# Saules_kolektoriaus_valdiklis_v1_22.net
KiCad netlist of a schematic drawn in EAGLE
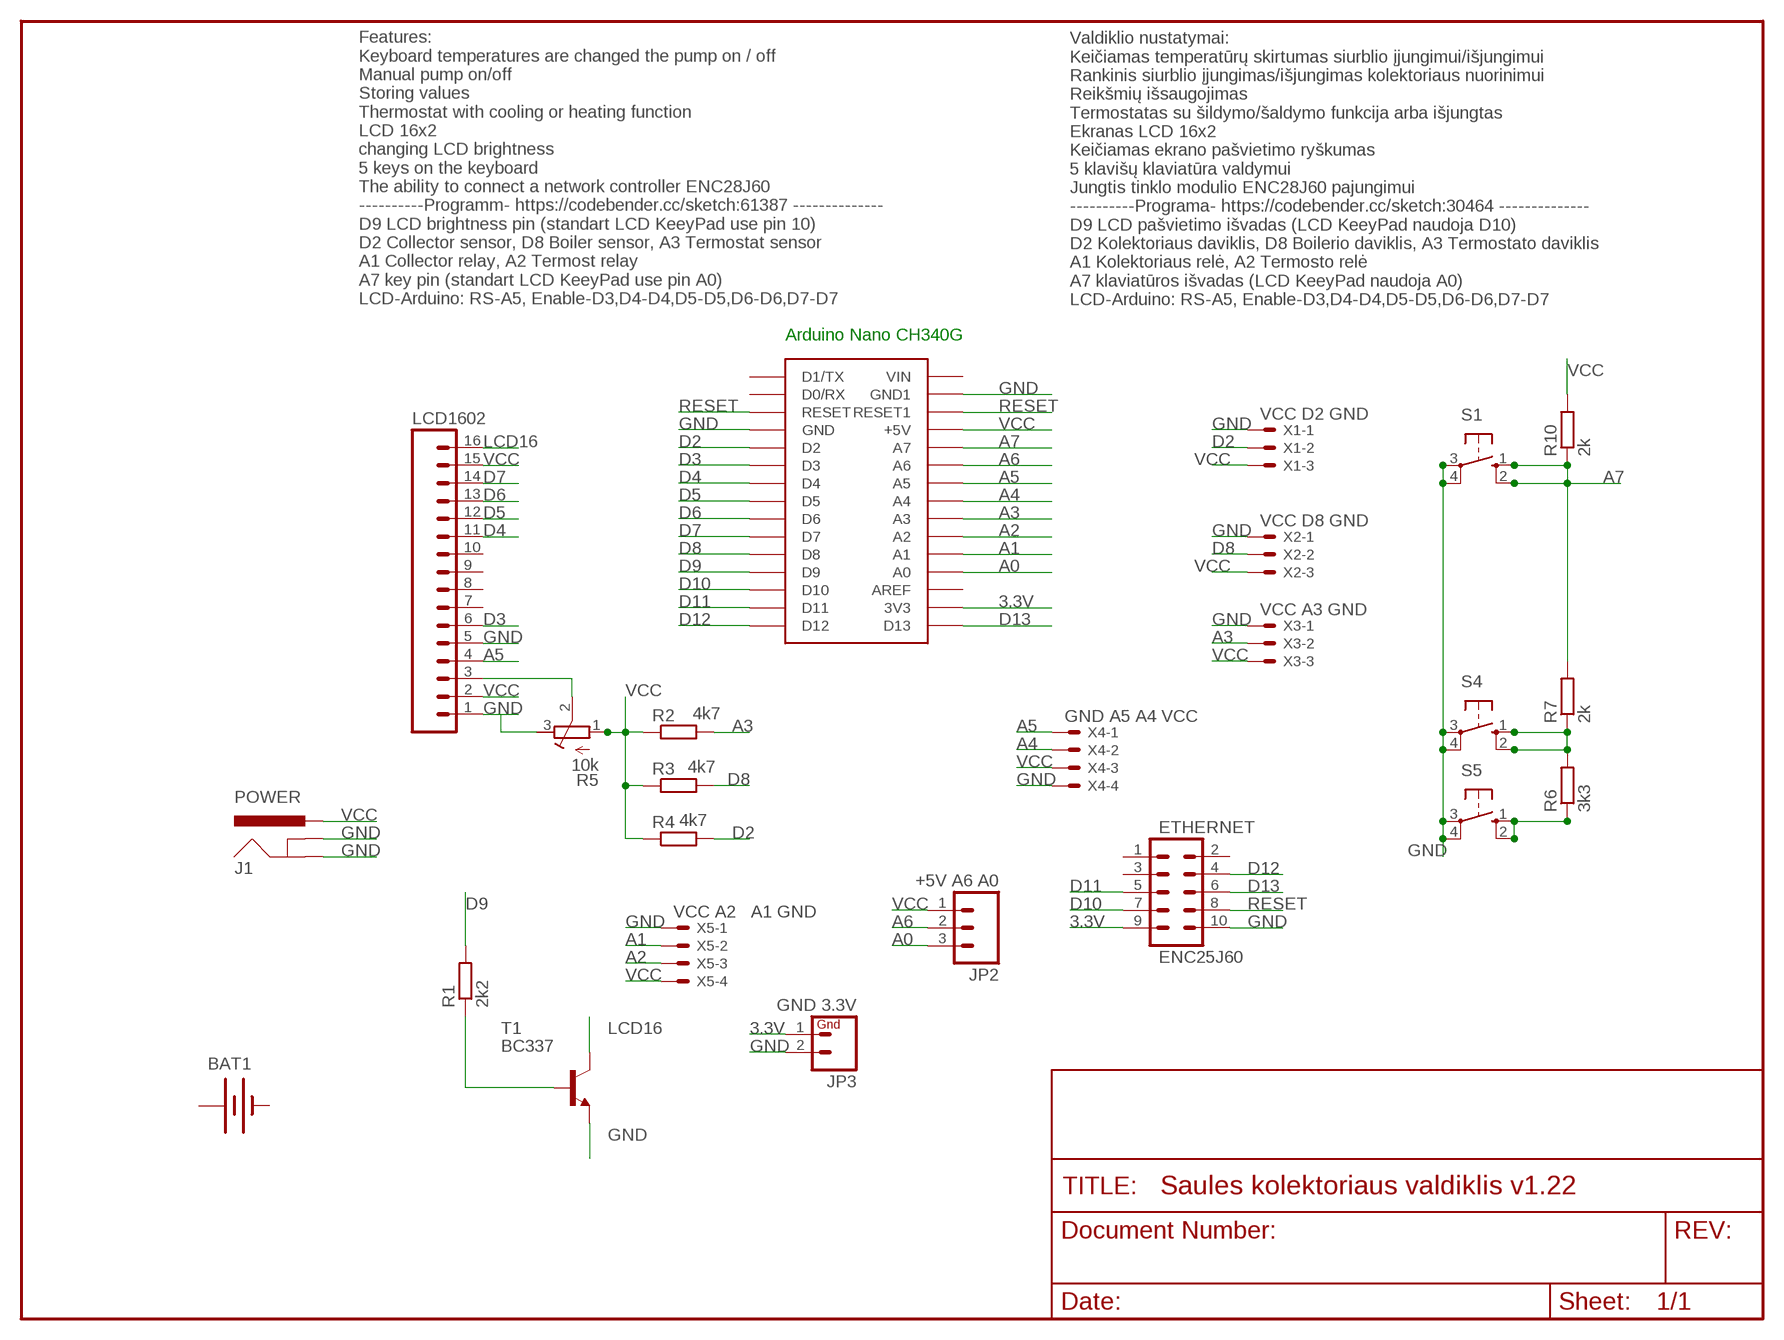
[diagram p0: schematic, sheet 1]

(export (version "E")
  (design (tool "Eeschema 10.0.6"))
  (components
    (comp (ref "ARDUINONANOCH340G")
      (value "ARDUINONANO")
      (footprint "eagle-import:PDIP-32")
      (libsource (lib "eagle-import") (part "ARDUINONANO"))
    )
    (comp (ref "BAT1")
      (value "BATTERY20PTH")
      (footprint "eagle-import:BATTCOM_20MM_PTH")
      (libsource (lib "eagle-import") (part "BATTERY20PTH"))
    )
    (comp (ref "ETHERNET")
      (value "ENC25J60")
      (footprint "eagle-import:AVR_ICSP")
      (libsource (lib "eagle-import") (part "M05X2PTH"))
    )
    (comp (ref "J1")
      (value "POWER")
      (footprint "eagle-import:POWER_JACK_PTH_LOCK")
      (libsource (lib "eagle-import") (part "POWER_JACKPTH_LOCK"))
    )
    (comp (ref "JP2")
      (value "+5V A6 A0")
      (footprint "eagle-import:1X03")
      (libsource (lib "eagle-import") (part "M03PTH"))
    )
    (comp (ref "JP3")
      (value "GND 3.3V")
      (footprint "eagle-import:1X02")
      (libsource (lib "eagle-import") (part "M02PTH"))
    )
    (comp (ref "LCD1602")
      (value "HEADER-16P-2.54")
      (footprint "eagle-import:16P-2.54")
      (libsource (lib "eagle-import") (part "HEADER-16P-2.54"))
    )
    (comp (ref "R1")
      (value "2k2")
      (footprint "eagle-import:0207_10")
      (libsource (lib "eagle-import") (part "R-EU_0207/10"))
    )
    (comp (ref "R2")
      (value "4k7")
      (footprint "eagle-import:0207_10")
      (libsource (lib "eagle-import") (part "R-EU_0207/10"))
    )
    (comp (ref "R3")
      (value "4k7")
      (footprint "eagle-import:0207_10")
      (libsource (lib "eagle-import") (part "R-EU_0207/10"))
    )
    (comp (ref "R4")
      (value "4k7")
      (footprint "eagle-import:0207_10")
      (libsource (lib "eagle-import") (part "R-EU_0207/10"))
    )
    (comp (ref "R5")
      (value "10k")
      (footprint "eagle-import:RTRIM64W")
      (libsource (lib "eagle-import") (part "R-TRIMM64W"))
    )
    (comp (ref "R6")
      (value "3k3")
      (footprint "eagle-import:0207_10")
      (libsource (lib "eagle-import") (part "R-EU_0207/10"))
    )
    (comp (ref "R7")
      (value "2k")
      (footprint "eagle-import:0207_10")
      (libsource (lib "eagle-import") (part "R-EU_0207/10"))
    )
    (comp (ref "R10")
      (value "2k")
      (footprint "eagle-import:0207_10")
      (libsource (lib "eagle-import") (part "R-EU_0207/10"))
    )
    (comp (ref "S1")
      (value "10-XX")
      (footprint "eagle-import:B3F-10XX")
      (fields (field (name "MPN") "B3F-1000"))
      (libsource (lib "eagle-import") (part "10-XX"))
    )
    (comp (ref "S4")
      (value "10-XX")
      (footprint "eagle-import:B3F-10XX")
      (fields (field (name "MPN") "B3F-1000"))
      (libsource (lib "eagle-import") (part "10-XX"))
    )
    (comp (ref "S5")
      (value "10-XX")
      (footprint "eagle-import:B3F-10XX")
      (fields (field (name "MPN") "B3F-1000"))
      (libsource (lib "eagle-import") (part "10-XX"))
    )
    (comp (ref "T1")
      (value "BC337")
      (footprint "eagle-import:TO92")
      (libsource (lib "eagle-import") (part "BC337"))
    )
    (comp (ref "X1")
      (value "VCC D2 GND")
      (footprint "eagle-import:22-23-2031")
      (fields (field (name "MF") "MOLEX") (field (name "MPN") "22-23-2031"))
      (libsource (lib "eagle-import") (part "22-23-2031"))
    )
    (comp (ref "X2")
      (value "VCC D8 GND")
      (footprint "eagle-import:22-23-2031")
      (fields (field (name "MF") "MOLEX") (field (name "MPN") "22-23-2031"))
      (libsource (lib "eagle-import") (part "22-23-2031"))
    )
    (comp (ref "X3")
      (value "VCC A3 GND")
      (footprint "eagle-import:22-23-2031")
      (fields (field (name "MF") "MOLEX") (field (name "MPN") "22-23-2031"))
      (libsource (lib "eagle-import") (part "22-23-2031"))
    )
    (comp (ref "X4")
      (value "GND A5 A4 VCC")
      (footprint "eagle-import:22-23-2041")
      (fields (field (name "MF") "MOLEX") (field (name "MPN") "22-23-2041"))
      (libsource (lib "eagle-import") (part "22-23-2041"))
    )
    (comp (ref "X5")
      (value "VCC A2 A1 GND")
      (footprint "eagle-import:22-23-2041")
      (fields (field (name "MF") "MOLEX") (field (name "MPN") "22-23-2041"))
      (libsource (lib "eagle-import") (part "22-23-2041"))
    )
  )
  (nets
    (net (code "1") (name "/+") (class "Default")
      (node (ref "BAT1") (pin "1") (pinfunction "+_1") (pintype "power_in"))
    )
    (net (code "2") (name "/-") (class "Default")
      (node (ref "BAT1") (pin "2") (pinfunction "-_2") (pintype "power_in"))
    )
    (net (code "3") (name "/3.3V") (class "Default")
      (node (ref "ARDUINONANOCH340G") (pin "3V3") (pinfunction "3V3_3V3") (pintype "bidirectional"))
      (node (ref "ETHERNET") (pin "9") (pinfunction "9_9") (pintype "passive"))
      (node (ref "JP3") (pin "1") (pinfunction "1_1") (pintype "passive"))
    )
    (net (code "4") (name "/A0") (class "Default")
      (node (ref "ARDUINONANOCH340G") (pin "A0") (pinfunction "A0_A0") (pintype "bidirectional"))
      (node (ref "JP2") (pin "3") (pinfunction "3_3") (pintype "passive"))
    )
    (net (code "5") (name "/A1") (class "Default")
      (node (ref "ARDUINONANOCH340G") (pin "A1") (pinfunction "A1_A1") (pintype "bidirectional"))
      (node (ref "X5") (pin "2") (pinfunction "S_2") (pintype "passive"))
    )
    (net (code "6") (name "/A2") (class "Default")
      (node (ref "ARDUINONANOCH340G") (pin "A2") (pinfunction "A2_A2") (pintype "bidirectional"))
      (node (ref "X5") (pin "3") (pinfunction "S_3") (pintype "passive"))
    )
    (net (code "7") (name "/A3") (class "Default")
      (node (ref "ARDUINONANOCH340G") (pin "A3") (pinfunction "A3_A3") (pintype "bidirectional"))
      (node (ref "R2") (pin "2") (pinfunction "2_2") (pintype "passive"))
      (node (ref "X3") (pin "2") (pinfunction "S_2") (pintype "passive"))
    )
    (net (code "8") (name "/A4") (class "Default")
      (node (ref "ARDUINONANOCH340G") (pin "A4") (pinfunction "A4_A4") (pintype "bidirectional"))
      (node (ref "X4") (pin "2") (pinfunction "S_2") (pintype "passive"))
    )
    (net (code "9") (name "/A5") (class "Default")
      (node (ref "ARDUINONANOCH340G") (pin "A5") (pinfunction "A5_A5") (pintype "bidirectional"))
      (node (ref "LCD1602") (pin "4") (pinfunction "4_4") (pintype "passive"))
      (node (ref "X4") (pin "1") (pinfunction "S_1") (pintype "passive"))
    )
    (net (code "10") (name "/A6") (class "Default")
      (node (ref "ARDUINONANOCH340G") (pin "A6") (pinfunction "A6_A6") (pintype "bidirectional"))
      (node (ref "JP2") (pin "2") (pinfunction "2_2") (pintype "passive"))
    )
    (net (code "11") (name "/A7") (class "Default")
      (node (ref "ARDUINONANOCH340G") (pin "A7") (pinfunction "A7_A7") (pintype "bidirectional"))
      (node (ref "R10") (pin "1") (pinfunction "1_1") (pintype "passive"))
      (node (ref "R7") (pin "2") (pinfunction "2_2") (pintype "passive"))
      (node (ref "S1") (pin "1") (pinfunction "S_1") (pintype "passive"))
      (node (ref "S1") (pin "2") (pinfunction "S1_2") (pintype "passive"))
    )
    (net (code "12") (name "/D2") (class "Default")
      (node (ref "ARDUINONANOCH340G") (pin "D2") (pinfunction "D2_D2") (pintype "bidirectional"))
      (node (ref "R4") (pin "2") (pinfunction "2_2") (pintype "passive"))
      (node (ref "X1") (pin "2") (pinfunction "S_2") (pintype "passive"))
    )
    (net (code "13") (name "/D3") (class "Default")
      (node (ref "ARDUINONANOCH340G") (pin "D3") (pinfunction "D3_D3") (pintype "bidirectional"))
      (node (ref "LCD1602") (pin "6") (pinfunction "6_6") (pintype "passive"))
    )
    (net (code "14") (name "/D4") (class "Default")
      (node (ref "ARDUINONANOCH340G") (pin "D4") (pinfunction "D4_D4") (pintype "bidirectional"))
      (node (ref "LCD1602") (pin "11") (pinfunction "11_11") (pintype "passive"))
    )
    (net (code "15") (name "/D5") (class "Default")
      (node (ref "ARDUINONANOCH340G") (pin "D5") (pinfunction "D5_D5") (pintype "bidirectional"))
      (node (ref "LCD1602") (pin "12") (pinfunction "12_12") (pintype "passive"))
    )
    (net (code "16") (name "/D6") (class "Default")
      (node (ref "ARDUINONANOCH340G") (pin "D6") (pinfunction "D6_D6") (pintype "bidirectional"))
      (node (ref "LCD1602") (pin "13") (pinfunction "13_13") (pintype "passive"))
    )
    (net (code "17") (name "/D7") (class "Default")
      (node (ref "ARDUINONANOCH340G") (pin "D7") (pinfunction "D7_D7") (pintype "bidirectional"))
      (node (ref "LCD1602") (pin "14") (pinfunction "14_14") (pintype "passive"))
    )
    (net (code "18") (name "/D8") (class "Default")
      (node (ref "ARDUINONANOCH340G") (pin "D8") (pinfunction "D8_D8") (pintype "bidirectional"))
      (node (ref "R3") (pin "2") (pinfunction "2_2") (pintype "passive"))
      (node (ref "X2") (pin "2") (pinfunction "S_2") (pintype "passive"))
    )
    (net (code "19") (name "/D9") (class "Default")
      (node (ref "ARDUINONANOCH340G") (pin "D9") (pinfunction "D9_D9") (pintype "bidirectional"))
      (node (ref "R1") (pin "2") (pinfunction "2_2") (pintype "passive"))
    )
    (net (code "20") (name "/D10") (class "Default")
      (node (ref "ARDUINONANOCH340G") (pin "D10") (pinfunction "D10_D10") (pintype "bidirectional"))
      (node (ref "ETHERNET") (pin "7") (pinfunction "7_7") (pintype "passive"))
    )
    (net (code "21") (name "/D11") (class "Default")
      (node (ref "ARDUINONANOCH340G") (pin "D11") (pinfunction "D11_D11") (pintype "bidirectional"))
      (node (ref "ETHERNET") (pin "5") (pinfunction "5_5") (pintype "passive"))
    )
    (net (code "22") (name "/D12") (class "Default")
      (node (ref "ARDUINONANOCH340G") (pin "D12") (pinfunction "D12_D12") (pintype "bidirectional"))
      (node (ref "ETHERNET") (pin "4") (pinfunction "4_4") (pintype "passive"))
    )
    (net (code "23") (name "/D13") (class "Default")
      (node (ref "ARDUINONANOCH340G") (pin "D13") (pinfunction "D13_D13") (pintype "bidirectional"))
      (node (ref "ETHERNET") (pin "6") (pinfunction "6_6") (pintype "passive"))
    )
    (net (code "24") (name "/GND") (class "Default")
      (node (ref "ARDUINONANOCH340G") (pin "GND") (pinfunction "GND_GND") (pintype "bidirectional"))
      (node (ref "ARDUINONANOCH340G") (pin "GND1") (pinfunction "GND1_GND1") (pintype "bidirectional"))
      (node (ref "ETHERNET") (pin "10") (pinfunction "10_10") (pintype "passive"))
      (node (ref "J1") (pin "GND") (pinfunction "GND_GND") (pintype "bidirectional"))
      (node (ref "J1") (pin "GNDBREAK") (pinfunction "GNDBREAK_GNDBREAK") (pintype "bidirectional"))
      (node (ref "JP3") (pin "2") (pinfunction "2_2") (pintype "passive"))
      (node (ref "LCD1602") (pin "1") (pinfunction "1_1") (pintype "passive"))
      (node (ref "LCD1602") (pin "5") (pinfunction "5_5") (pintype "passive"))
      (node (ref "R5") (pin "3") (pinfunction "A_3") (pintype "passive"))
      (node (ref "S1") (pin "3") (pinfunction "P_3") (pintype "passive"))
      (node (ref "S1") (pin "4") (pinfunction "P1_4") (pintype "passive"))
      (node (ref "S4") (pin "3") (pinfunction "P_3") (pintype "passive"))
      (node (ref "S4") (pin "4") (pinfunction "P1_4") (pintype "passive"))
      (node (ref "S5") (pin "3") (pinfunction "P_3") (pintype "passive"))
      (node (ref "S5") (pin "4") (pinfunction "P1_4") (pintype "passive"))
      (node (ref "T1") (pin "1") (pinfunction "E_1") (pintype "passive"))
      (node (ref "X1") (pin "1") (pinfunction "S_1") (pintype "passive"))
      (node (ref "X2") (pin "1") (pinfunction "S_1") (pintype "passive"))
      (node (ref "X3") (pin "1") (pinfunction "S_1") (pintype "passive"))
      (node (ref "X4") (pin "4") (pinfunction "S_4") (pintype "passive"))
      (node (ref "X5") (pin "1") (pinfunction "S_1") (pintype "passive"))
    )
    (net (code "25") (name "/LCD16") (class "Default")
      (node (ref "LCD1602") (pin "16") (pinfunction "16_16") (pintype "passive"))
      (node (ref "T1") (pin "3") (pinfunction "C_3") (pintype "passive"))
    )
    (net (code "26") (name "/RESET") (class "Default")
      (node (ref "ARDUINONANOCH340G") (pin "RESET") (pinfunction "RESET_RESET") (pintype "bidirectional"))
      (node (ref "ARDUINONANOCH340G") (pin "RESET1") (pinfunction "RESET1_RESET1") (pintype "bidirectional"))
      (node (ref "ETHERNET") (pin "8") (pinfunction "8_8") (pintype "passive"))
    )
    (net (code "27") (name "/VCC") (class "Default")
      (node (ref "ARDUINONANOCH340G") (pin "+5V") (pinfunction "+5V_+5V") (pintype "bidirectional"))
      (node (ref "J1") (pin "PWR") (pinfunction "PWR_PWR") (pintype "bidirectional"))
      (node (ref "JP2") (pin "1") (pinfunction "1_1") (pintype "passive"))
      (node (ref "LCD1602") (pin "15") (pinfunction "15_15") (pintype "passive"))
      (node (ref "LCD1602") (pin "2") (pinfunction "2_2") (pintype "passive"))
      (node (ref "R10") (pin "2") (pinfunction "2_2") (pintype "passive"))
      (node (ref "R2") (pin "1") (pinfunction "1_1") (pintype "passive"))
      (node (ref "R3") (pin "1") (pinfunction "1_1") (pintype "passive"))
      (node (ref "R4") (pin "1") (pinfunction "1_1") (pintype "passive"))
      (node (ref "R5") (pin "1") (pinfunction "E_1") (pintype "passive"))
      (node (ref "X1") (pin "3") (pinfunction "S_3") (pintype "passive"))
      (node (ref "X2") (pin "3") (pinfunction "S_3") (pintype "passive"))
      (node (ref "X3") (pin "3") (pinfunction "S_3") (pintype "passive"))
      (node (ref "X4") (pin "3") (pinfunction "S_3") (pintype "passive"))
      (node (ref "X5") (pin "4") (pinfunction "S_4") (pintype "passive"))
    )
    (net (code "28") (name "Net-(R5-S)") (class "Default")
      (node (ref "LCD1602") (pin "3") (pinfunction "3_3") (pintype "passive"))
      (node (ref "R5") (pin "2") (pinfunction "S_2") (pintype "passive"))
    )
    (net (code "29") (name "Net-(S4-S)") (class "Default")
      (node (ref "R6") (pin "2") (pinfunction "2_2") (pintype "passive"))
      (node (ref "R7") (pin "1") (pinfunction "1_1") (pintype "passive"))
      (node (ref "S4") (pin "1") (pinfunction "S_1") (pintype "passive"))
      (node (ref "S4") (pin "2") (pinfunction "S1_2") (pintype "passive"))
    )
    (net (code "30") (name "Net-(S5-S)") (class "Default")
      (node (ref "R6") (pin "1") (pinfunction "1_1") (pintype "passive"))
      (node (ref "S5") (pin "1") (pinfunction "S_1") (pintype "passive"))
      (node (ref "S5") (pin "2") (pinfunction "S1_2") (pintype "passive"))
    )
    (net (code "31") (name "Net-(T1-B)") (class "Default")
      (node (ref "R1") (pin "1") (pinfunction "1_1") (pintype "passive"))
      (node (ref "T1") (pin "2") (pinfunction "B_2") (pintype "passive"))
    )
    (net (code "32") (name "unconnected-(ARDUINONANOCH340G-PadAREF)") (class "Default")
      (node (ref "ARDUINONANOCH340G") (pin "AREF") (pinfunction "AREF_AREF") (pintype "bidirectional"))
    )
    (net (code "33") (name "unconnected-(ARDUINONANOCH340G-PadD0{slash}RX)") (class "Default")
      (node (ref "ARDUINONANOCH340G") (pin "D0/RX") (pinfunction "D0/RX_D0/RX") (pintype "bidirectional"))
    )
    (net (code "34") (name "unconnected-(ARDUINONANOCH340G-PadD1{slash}TX)") (class "Default")
      (node (ref "ARDUINONANOCH340G") (pin "D1/TX") (pinfunction "D1/TX_D1/TX") (pintype "bidirectional"))
    )
    (net (code "35") (name "unconnected-(ARDUINONANOCH340G-PadVIN)") (class "Default")
      (node (ref "ARDUINONANOCH340G") (pin "VIN") (pinfunction "VIN_VIN") (pintype "bidirectional"))
    )
    (net (code "36") (name "unconnected-(ETHERNET-Pad1)") (class "Default")
      (node (ref "ETHERNET") (pin "1") (pinfunction "1_1") (pintype "passive"))
    )
    (net (code "37") (name "unconnected-(ETHERNET-Pad2)") (class "Default")
      (node (ref "ETHERNET") (pin "2") (pinfunction "2_2") (pintype "passive"))
    )
    (net (code "38") (name "unconnected-(ETHERNET-Pad3)") (class "Default")
      (node (ref "ETHERNET") (pin "3") (pinfunction "3_3") (pintype "passive"))
    )
    (net (code "39") (name "unconnected-(LCD1602-Pad7)") (class "Default")
      (node (ref "LCD1602") (pin "7") (pinfunction "7_7") (pintype "passive"))
    )
    (net (code "40") (name "unconnected-(LCD1602-Pad8)") (class "Default")
      (node (ref "LCD1602") (pin "8") (pinfunction "8_8") (pintype "passive"))
    )
    (net (code "41") (name "unconnected-(LCD1602-Pad9)") (class "Default")
      (node (ref "LCD1602") (pin "9") (pinfunction "9_9") (pintype "passive"))
    )
    (net (code "42") (name "unconnected-(LCD1602-Pad10)") (class "Default")
      (node (ref "LCD1602") (pin "10") (pinfunction "10_10") (pintype "passive"))
    )
  )
)
